# hijack-fram_C.net
KiCad netlist of a schematic drawn in EAGLE
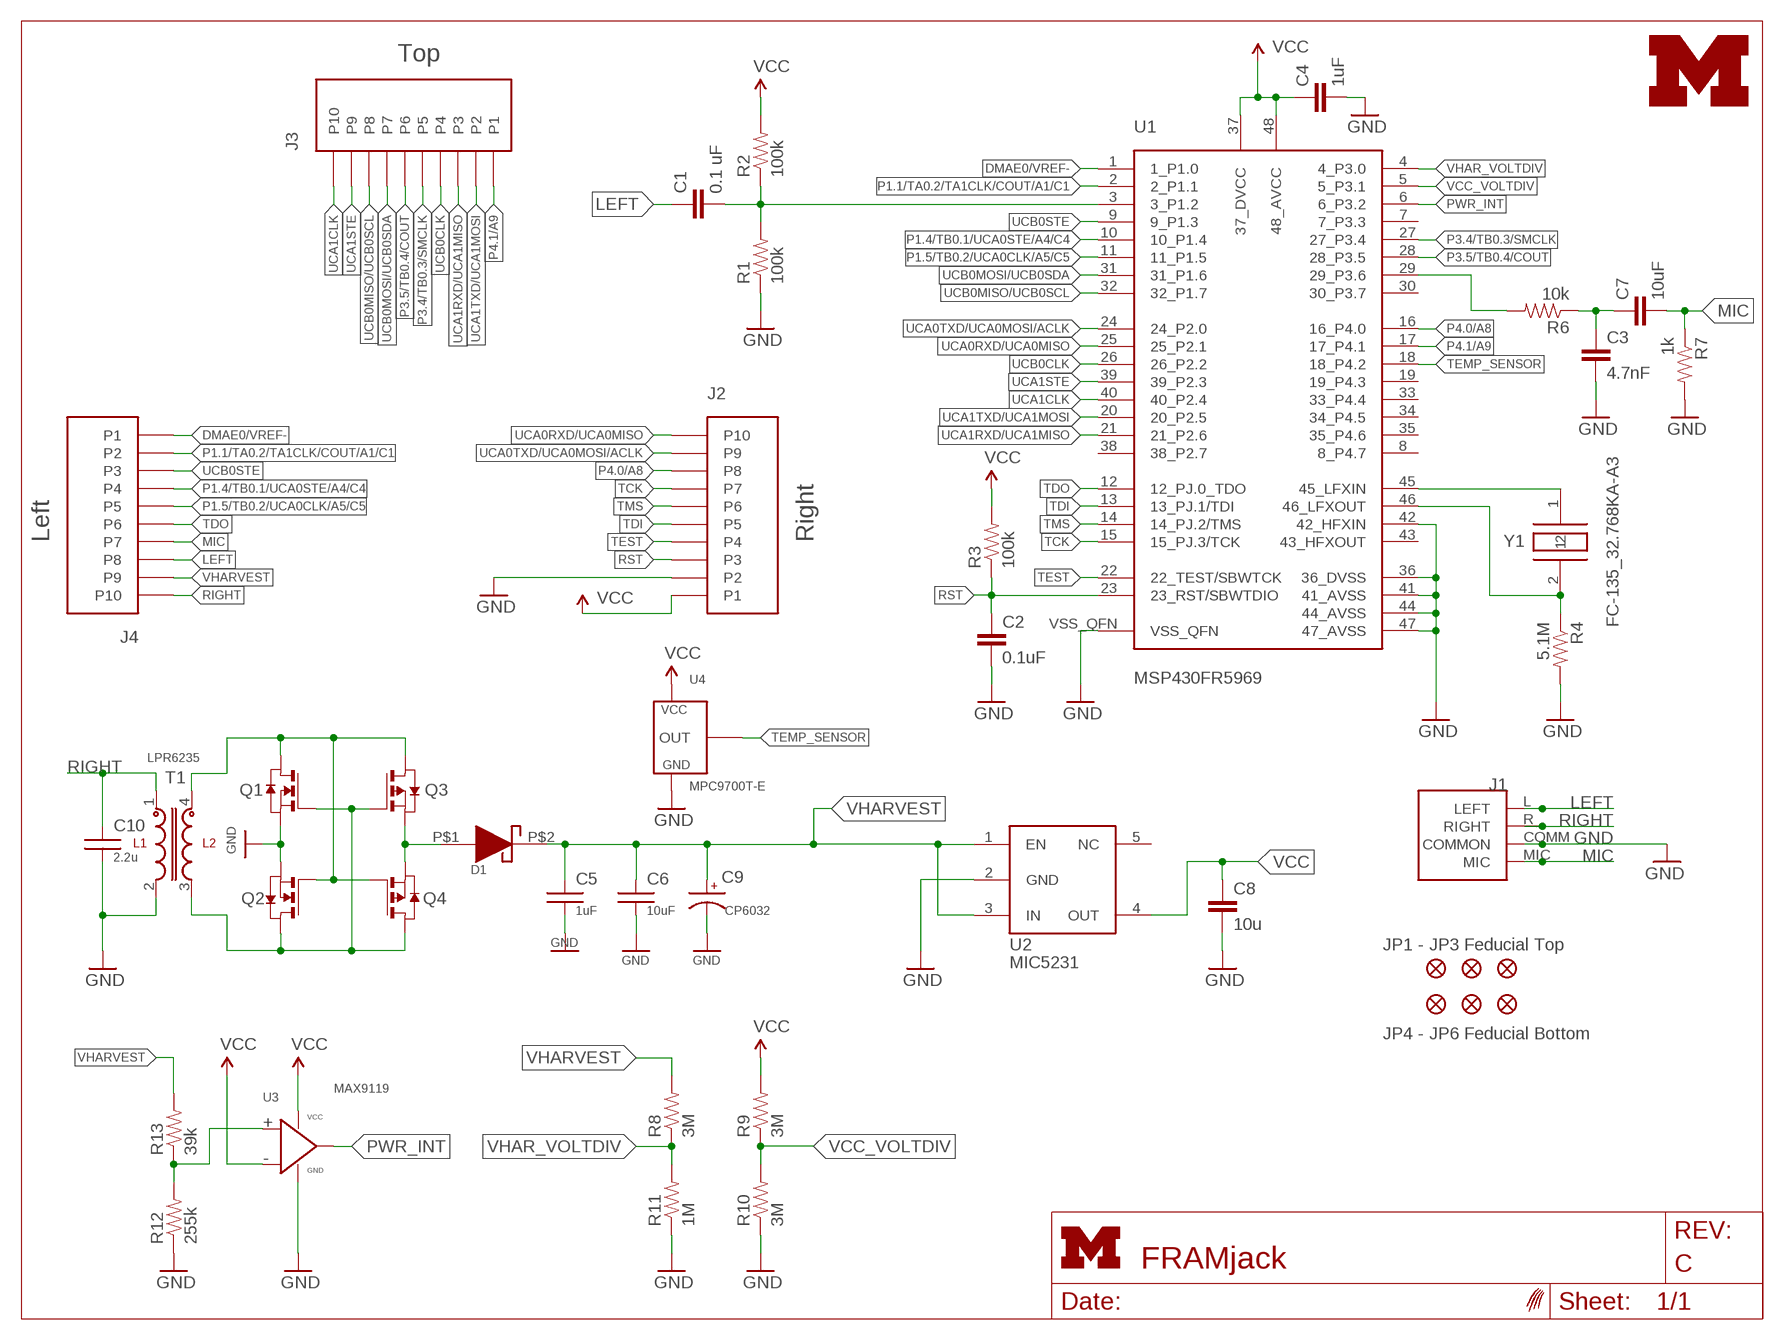
[diagram p0: schematic, sheet 1]

(export (version "E")
  (design (tool "Eeschema 10.0.6"))
  (components
    (comp (ref "C1")
      (value "0.1 uF")
      (footprint "eagle-import:0603-CAP")
      (libsource (lib "eagle-import") (part "CAP0603-CAP"))
    )
    (comp (ref "C2")
      (value "0.1uF")
      (footprint "eagle-import:0603-CAP")
      (libsource (lib "eagle-import") (part "CAP0603-CAP"))
    )
    (comp (ref "C3")
      (value "4.7nF")
      (footprint "eagle-import:0603-CAP")
      (libsource (lib "eagle-import") (part "CAP0603-CAP"))
    )
    (comp (ref "C4")
      (value "1uF")
      (footprint "eagle-import:0603-CAP")
      (libsource (lib "eagle-import") (part "CAP0603-CAP"))
    )
    (comp (ref "C5")
      (value "1uF")
      (footprint "eagle-import:C0603")
      (libsource (lib "eagle-import") (part "C0603"))
    )
    (comp (ref "C6")
      (value "10uF")
      (footprint "eagle-import:C0603")
      (libsource (lib "eagle-import") (part "C0603"))
    )
    (comp (ref "C7")
      (value "10uF")
      (footprint "eagle-import:0603-CAP")
      (libsource (lib "eagle-import") (part "CAP0603-CAP"))
    )
    (comp (ref "C8")
      (value "10u")
      (footprint "eagle-import:C0603")
      (libsource (lib "eagle-import") (part "C-EUC0603"))
    )
    (comp (ref "C9")
      (value "CP6032")
      (footprint "eagle-import:CT6032")
      (libsource (lib "eagle-import") (part "CP6032"))
    )
    (comp (ref "C10")
      (value "2.2u")
      (footprint "eagle-import:C0603")
      (libsource (lib "eagle-import") (part "C0603"))
    )
    (comp (ref "D1")
      (value "B5818WS-SCHOTTKY-DIODE")
      (footprint "eagle-import:SOD-323")
      (libsource (lib "eagle-import") (part "B5818WS-SCHOTTKY-DIODE"))
    )
    (comp (ref "J1")
      (value "3.5JACK4CONNSUNSTONE_QUICKTURN")
      (footprint "eagle-import:PLUGBOARDCONNECTOR_SUNSTONE")
      (libsource (lib "eagle-import") (part "3.5JACK4CONNSUNSTONE_QUICKTURN"))
    )
    (comp (ref "J2")
      (value "HEADER10POS")
      (footprint "eagle-import:10PIN2MMHEADER")
      (libsource (lib "eagle-import") (part "HEADER10POS"))
    )
    (comp (ref "J3")
      (value "HEADER10POS")
      (footprint "eagle-import:10PIN2MMHEADER")
      (libsource (lib "eagle-import") (part "HEADER10POS"))
    )
    (comp (ref "J4")
      (value "HEADER10POS")
      (footprint "eagle-import:10PIN2MMHEADER")
      (libsource (lib "eagle-import") (part "HEADER10POS"))
    )
    (comp (ref "JP1")
      (value "FIDUCIAL1X2")
      (footprint "eagle-import:FIDUCIAL-1X2")
      (libsource (lib "eagle-import") (part "FIDUCIAL1X2"))
    )
    (comp (ref "JP2")
      (value "FIDUCIAL1X2")
      (footprint "eagle-import:FIDUCIAL-1X2")
      (libsource (lib "eagle-import") (part "FIDUCIAL1X2"))
    )
    (comp (ref "JP3")
      (value "FIDUCIAL1X2")
      (footprint "eagle-import:FIDUCIAL-1X2")
      (libsource (lib "eagle-import") (part "FIDUCIAL1X2"))
    )
    (comp (ref "JP4")
      (value "FIDUCIAL1X2")
      (footprint "eagle-import:FIDUCIAL-1X2")
      (libsource (lib "eagle-import") (part "FIDUCIAL1X2"))
    )
    (comp (ref "JP5")
      (value "FIDUCIAL1X2")
      (footprint "eagle-import:FIDUCIAL-1X2")
      (libsource (lib "eagle-import") (part "FIDUCIAL1X2"))
    )
    (comp (ref "JP6")
      (value "FIDUCIAL1X2")
      (footprint "eagle-import:FIDUCIAL-1X2")
      (libsource (lib "eagle-import") (part "FIDUCIAL1X2"))
    )
    (comp (ref "Q1")
      (value "NMOSSOT23")
      (footprint "eagle-import:SOT-23")
      (libsource (lib "eagle-import") (part "NMOSSOT23"))
    )
    (comp (ref "Q2")
      (value "NMOSSOT23")
      (footprint "eagle-import:SOT-23")
      (libsource (lib "eagle-import") (part "NMOSSOT23"))
    )
    (comp (ref "Q3")
      (value "PMOSSOT23")
      (footprint "eagle-import:SOT-23")
      (libsource (lib "eagle-import") (part "PMOSSOT23"))
    )
    (comp (ref "Q4")
      (value "PMOSSOT23")
      (footprint "eagle-import:SOT-23")
      (libsource (lib "eagle-import") (part "PMOSSOT23"))
    )
    (comp (ref "R1")
      (value "100k")
      (footprint "eagle-import:0603-RES")
      (libsource (lib "eagle-import") (part "RESISTOR0603-RES"))
    )
    (comp (ref "R2")
      (value "100k")
      (footprint "eagle-import:0603-RES")
      (libsource (lib "eagle-import") (part "RESISTOR0603-RES"))
    )
    (comp (ref "R3")
      (value "100k")
      (footprint "eagle-import:0603-RES")
      (libsource (lib "eagle-import") (part "RESISTOR0603-RES"))
    )
    (comp (ref "R4")
      (value "5.1M")
      (footprint "eagle-import:0603-RES")
      (libsource (lib "eagle-import") (part "RESISTOR0603-RES"))
    )
    (comp (ref "R6")
      (value "10k")
      (footprint "eagle-import:0603-RES")
      (libsource (lib "eagle-import") (part "RESISTOR0603-RES"))
    )
    (comp (ref "R7")
      (value "1k")
      (footprint "eagle-import:0603-RES")
      (libsource (lib "eagle-import") (part "RESISTOR0603-RES"))
    )
    (comp (ref "R8")
      (value "3M")
      (footprint "eagle-import:0603-RES")
      (libsource (lib "eagle-import") (part "RESISTOR0603-RES"))
    )
    (comp (ref "R9")
      (value "3M")
      (footprint "eagle-import:0603-RES")
      (libsource (lib "eagle-import") (part "RESISTOR0603-RES"))
    )
    (comp (ref "R10")
      (value "3M")
      (footprint "eagle-import:0603-RES")
      (libsource (lib "eagle-import") (part "RESISTOR0603-RES"))
    )
    (comp (ref "R11")
      (value "1M")
      (footprint "eagle-import:0603-RES")
      (libsource (lib "eagle-import") (part "RESISTOR0603-RES"))
    )
    (comp (ref "R12")
      (value "255k")
      (footprint "eagle-import:0603-RES")
      (libsource (lib "eagle-import") (part "RESISTOR0603-RES"))
    )
    (comp (ref "R13")
      (value "39k")
      (footprint "eagle-import:0603-RES")
      (libsource (lib "eagle-import") (part "RESISTOR0603-RES"))
    )
    (comp (ref "T1")
      (value "LPR6235")
      (footprint "eagle-import:LPR6235")
      (libsource (lib "eagle-import") (part "LPR6235"))
    )
    (comp (ref "U$1")
      (value "WOLVERINE")
      (footprint "eagle-import:WOLVERINE")
      (libsource (lib "eagle-import") (part "WOLVERINE"))
    )
    (comp (ref "U$4")
      (value "UMICH_SOLID_SMALL")
      (footprint "eagle-import:UMICH_SOLID_75MIL")
      (libsource (lib "eagle-import") (part "UMICH_SOLID_SMALL"))
    )
    (comp (ref "U1")
      (value "MSP430FR5969")
      (footprint "eagle-import:RGZ(S-PQFP-N48)")
      (libsource (lib "eagle-import") (part "MSP430FR5969"))
    )
    (comp (ref "U2")
      (value "MIC5231")
      (footprint "eagle-import:SOT23-5")
      (libsource (lib "eagle-import") (part "MIC5231"))
    )
    (comp (ref "U3")
      (value "MAX9119")
      (footprint "eagle-import:SC70-5")
      (libsource (lib "eagle-import") (part "MAX9119"))
    )
    (comp (ref "U4")
      (value "MPC9700T-E")
      (footprint "eagle-import:SOT-23")
      (libsource (lib "eagle-import") (part "MPC9700T-E"))
    )
    (comp (ref "Y1")
      (value "FC-135_32.768KA-A3")
      (footprint "eagle-import:FC-135")
      (libsource (lib "eagle-import") (part "FC-135_32.768KA-A3"))
    )
  )
  (nets
    (net (code "1") (name "DMAE0{slash}VREF-") (class "Default")
      (node (ref "J4") (pin "P1") (pinfunction "P1_P1") (pintype "bidirectional"))
      (node (ref "U1") (pin "1") (pinfunction "1_P1.0_1") (pintype "bidirectional"))
    )
    (net (code "2") (name "GND") (class "Default")
      (node (ref "C10") (pin "2") (pinfunction "2_2") (pintype "bidirectional"))
      (node (ref "C2") (pin "2") (pinfunction "2_2") (pintype "passive"))
      (node (ref "C3") (pin "2") (pinfunction "2_2") (pintype "passive"))
      (node (ref "C4") (pin "2") (pinfunction "2_2") (pintype "passive"))
      (node (ref "C5") (pin "2") (pinfunction "2_2") (pintype "bidirectional"))
      (node (ref "C6") (pin "2") (pinfunction "2_2") (pintype "bidirectional"))
      (node (ref "C8") (pin "2") (pinfunction "2_2") (pintype "passive"))
      (node (ref "C9") (pin "-") (pinfunction "-_-") (pintype "bidirectional"))
      (node (ref "J1") (pin "COMM") (pinfunction "COMMON_COMM") (pintype "power_in"))
      (node (ref "J2") (pin "P2") (pinfunction "P2_P2") (pintype "bidirectional"))
      (node (ref "Q1") (pin "2") (pinfunction "S_2") (pintype "passive"))
      (node (ref "Q2") (pin "2") (pinfunction "S_2") (pintype "passive"))
      (node (ref "R1") (pin "1") (pinfunction "1_1") (pintype "passive"))
      (node (ref "R10") (pin "1") (pinfunction "1_1") (pintype "passive"))
      (node (ref "R11") (pin "1") (pinfunction "1_1") (pintype "passive"))
      (node (ref "R12") (pin "1") (pinfunction "1_1") (pintype "passive"))
      (node (ref "R4") (pin "2") (pinfunction "2_2") (pintype "passive"))
      (node (ref "R7") (pin "2") (pinfunction "2_2") (pintype "passive"))
      (node (ref "T1") (pin "2") (pinfunction "2_2") (pintype "bidirectional"))
      (node (ref "U1") (pin "36") (pinfunction "36_DVSS_36") (pintype "bidirectional"))
      (node (ref "U1") (pin "41") (pinfunction "41_AVSS_41") (pintype "bidirectional"))
      (node (ref "U1") (pin "42") (pinfunction "42_HFXIN_42") (pintype "bidirectional"))
      (node (ref "U1") (pin "44") (pinfunction "44_AVSS_44") (pintype "bidirectional"))
      (node (ref "U1") (pin "47") (pinfunction "47_AVSS_47") (pintype "bidirectional"))
      (node (ref "U1") (pin "VSS_QFN") (pinfunction "VSS_QFN_VSS_QFN") (pintype "bidirectional"))
      (node (ref "U2") (pin "2") (pinfunction "GND_2") (pintype "bidirectional"))
      (node (ref "U3") (pin "2") (pinfunction "GND_2") (pintype "bidirectional"))
      (node (ref "U4") (pin "GND") (pinfunction "GND_GND") (pintype "bidirectional"))
    )
    (net (code "3") (name "LEFT") (class "Default")
      (node (ref "C1") (pin "1") (pinfunction "1_1") (pintype "passive"))
      (node (ref "J1") (pin "L") (pinfunction "LEFT_L") (pintype "output"))
      (node (ref "J4") (pin "P8") (pinfunction "P8_P8") (pintype "bidirectional"))
    )
    (net (code "4") (name "MIC") (class "Default")
      (node (ref "C7") (pin "2") (pinfunction "2_2") (pintype "passive"))
      (node (ref "J1") (pin "MIC") (pinfunction "MIC_MIC") (pintype "input"))
      (node (ref "J4") (pin "P7") (pinfunction "P7_P7") (pintype "bidirectional"))
      (node (ref "R7") (pin "1") (pinfunction "1_1") (pintype "passive"))
    )
    (net (code "5") (name "Net-(C3-Pad1)") (class "Default")
      (node (ref "C3") (pin "1") (pinfunction "1_1") (pintype "passive"))
      (node (ref "C7") (pin "1") (pinfunction "1_1") (pintype "passive"))
      (node (ref "R6") (pin "1") (pinfunction "1_1") (pintype "passive"))
    )
    (net (code "6") (name "Net-(D1-A)") (class "Default")
      (node (ref "D1") (pin "P$1") (pinfunction "A_P$1") (pintype "bidirectional"))
      (node (ref "Q3") (pin "2") (pinfunction "S_2") (pintype "passive"))
      (node (ref "Q4") (pin "2") (pinfunction "S_2") (pintype "passive"))
    )
    (net (code "7") (name "Net-(Q1-D)") (class "Default")
      (node (ref "Q1") (pin "1") (pinfunction "D_1") (pintype "passive"))
      (node (ref "Q2") (pin "3") (pinfunction "G_3") (pintype "passive"))
      (node (ref "Q3") (pin "1") (pinfunction "D_1") (pintype "passive"))
      (node (ref "Q4") (pin "3") (pinfunction "G_3") (pintype "passive"))
      (node (ref "T1") (pin "4") (pinfunction "4_4") (pintype "bidirectional"))
    )
    (net (code "8") (name "Net-(Q1-G)") (class "Default")
      (node (ref "Q1") (pin "3") (pinfunction "G_3") (pintype "passive"))
      (node (ref "Q2") (pin "1") (pinfunction "D_1") (pintype "passive"))
      (node (ref "Q3") (pin "3") (pinfunction "G_3") (pintype "passive"))
      (node (ref "Q4") (pin "1") (pinfunction "D_1") (pintype "passive"))
      (node (ref "T1") (pin "3") (pinfunction "3_3") (pintype "bidirectional"))
    )
    (net (code "9") (name "Net-(U1-3_P1.2)") (class "Default")
      (node (ref "C1") (pin "2") (pinfunction "2_2") (pintype "passive"))
      (node (ref "R1") (pin "2") (pinfunction "2_2") (pintype "passive"))
      (node (ref "R2") (pin "1") (pinfunction "1_1") (pintype "passive"))
      (node (ref "U1") (pin "3") (pinfunction "3_P1.2_3") (pintype "bidirectional"))
    )
    (net (code "10") (name "Net-(U1-29_P3.6)") (class "Default")
      (node (ref "R6") (pin "2") (pinfunction "2_2") (pintype "passive"))
      (node (ref "U1") (pin "29") (pinfunction "29_P3.6_29") (pintype "bidirectional"))
    )
    (net (code "11") (name "Net-(U1-45_LFXIN)") (class "Default")
      (node (ref "U1") (pin "45") (pinfunction "45_LFXIN_45") (pintype "bidirectional"))
      (node (ref "Y1") (pin "1") (pinfunction "1_1") (pintype "bidirectional"))
    )
    (net (code "12") (name "Net-(U1-46_LFXOUT)") (class "Default")
      (node (ref "R4") (pin "1") (pinfunction "1_1") (pintype "passive"))
      (node (ref "U1") (pin "46") (pinfunction "46_LFXOUT_46") (pintype "bidirectional"))
      (node (ref "Y1") (pin "2") (pinfunction "2_2") (pintype "bidirectional"))
    )
    (net (code "13") (name "Net-(U3-IN+)") (class "Default")
      (node (ref "R12") (pin "2") (pinfunction "2_2") (pintype "passive"))
      (node (ref "R13") (pin "1") (pinfunction "1_1") (pintype "passive"))
      (node (ref "U3") (pin "3") (pinfunction "IN+_3") (pintype "bidirectional"))
    )
    (net (code "14") (name "P1.1{slash}TA0.2{slash}TA1CLK{slash}COUT{slash}A1{slash}C1") (class "Default")
      (node (ref "J4") (pin "P2") (pinfunction "P2_P2") (pintype "bidirectional"))
      (node (ref "U1") (pin "2") (pinfunction "2_P1.1_2") (pintype "bidirectional"))
    )
    (net (code "15") (name "P1.4{slash}TB0.1{slash}UCA0STE{slash}A4{slash}C4") (class "Default")
      (node (ref "J4") (pin "P4") (pinfunction "P4_P4") (pintype "bidirectional"))
      (node (ref "U1") (pin "10") (pinfunction "10_P1.4_10") (pintype "bidirectional"))
    )
    (net (code "16") (name "P1.5{slash}TB0.2{slash}UCA0CLK{slash}A5{slash}C5") (class "Default")
      (node (ref "J4") (pin "P5") (pinfunction "P5_P5") (pintype "bidirectional"))
      (node (ref "U1") (pin "11") (pinfunction "11_P1.5_11") (pintype "bidirectional"))
    )
    (net (code "17") (name "P3.4{slash}TB0.3{slash}SMCLK") (class "Default")
      (node (ref "J3") (pin "P5") (pinfunction "P5_P5") (pintype "bidirectional"))
      (node (ref "U1") (pin "27") (pinfunction "27_P3.4_27") (pintype "bidirectional"))
    )
    (net (code "18") (name "P3.5{slash}TB0.4{slash}COUT") (class "Default")
      (node (ref "J3") (pin "P6") (pinfunction "P6_P6") (pintype "bidirectional"))
      (node (ref "U1") (pin "28") (pinfunction "28_P3.5_28") (pintype "bidirectional"))
    )
    (net (code "19") (name "P4.0{slash}A8") (class "Default")
      (node (ref "J2") (pin "P8") (pinfunction "P8_P8") (pintype "bidirectional"))
      (node (ref "U1") (pin "16") (pinfunction "16_P4.0_16") (pintype "bidirectional"))
    )
    (net (code "20") (name "P4.1{slash}A9") (class "Default")
      (node (ref "J3") (pin "P1") (pinfunction "P1_P1") (pintype "bidirectional"))
      (node (ref "U1") (pin "17") (pinfunction "17_P4.1_17") (pintype "bidirectional"))
    )
    (net (code "21") (name "PWR_INT") (class "Default")
      (node (ref "U1") (pin "6") (pinfunction "6_P3.2_6") (pintype "bidirectional"))
      (node (ref "U3") (pin "1") (pinfunction "OUT_1") (pintype "bidirectional"))
    )
    (net (code "22") (name "RIGHT") (class "Default")
      (node (ref "C10") (pin "1") (pinfunction "1_1") (pintype "bidirectional"))
      (node (ref "J1") (pin "R") (pinfunction "RIGHT_R") (pintype "output"))
      (node (ref "J4") (pin "P10") (pinfunction "P10_P10") (pintype "bidirectional"))
      (node (ref "T1") (pin "1") (pinfunction "1_1") (pintype "bidirectional"))
    )
    (net (code "23") (name "RST") (class "Default")
      (node (ref "C2") (pin "1") (pinfunction "1_1") (pintype "passive"))
      (node (ref "J2") (pin "P3") (pinfunction "P3_P3") (pintype "bidirectional"))
      (node (ref "R3") (pin "1") (pinfunction "1_1") (pintype "passive"))
      (node (ref "U1") (pin "23") (pinfunction "23_RST/SBWTDIO_23") (pintype "bidirectional"))
    )
    (net (code "24") (name "TCK") (class "Default")
      (node (ref "J2") (pin "P7") (pinfunction "P7_P7") (pintype "bidirectional"))
      (node (ref "U1") (pin "15") (pinfunction "15_PJ.3/TCK_15") (pintype "bidirectional"))
    )
    (net (code "25") (name "TDI") (class "Default")
      (node (ref "J2") (pin "P5") (pinfunction "P5_P5") (pintype "bidirectional"))
      (node (ref "U1") (pin "13") (pinfunction "13_PJ.1/TDI_13") (pintype "bidirectional"))
    )
    (net (code "26") (name "TDO") (class "Default")
      (node (ref "J4") (pin "P6") (pinfunction "P6_P6") (pintype "bidirectional"))
      (node (ref "U1") (pin "12") (pinfunction "12_PJ.0_TDO_12") (pintype "bidirectional"))
    )
    (net (code "27") (name "TEMP_SENSOR") (class "Default")
      (node (ref "U1") (pin "18") (pinfunction "18_P4.2_18") (pintype "bidirectional"))
      (node (ref "U4") (pin "VOUT") (pinfunction "OUT_VOUT") (pintype "bidirectional"))
    )
    (net (code "28") (name "TEST") (class "Default")
      (node (ref "J2") (pin "P4") (pinfunction "P4_P4") (pintype "bidirectional"))
      (node (ref "U1") (pin "22") (pinfunction "22_TEST/SBWTCK_22") (pintype "bidirectional"))
    )
    (net (code "29") (name "TMS") (class "Default")
      (node (ref "J2") (pin "P6") (pinfunction "P6_P6") (pintype "bidirectional"))
      (node (ref "U1") (pin "14") (pinfunction "14_PJ.2/TMS_14") (pintype "bidirectional"))
    )
    (net (code "30") (name "UCA0RXD{slash}UCA0MISO") (class "Default")
      (node (ref "J2") (pin "P10") (pinfunction "P10_P10") (pintype "bidirectional"))
      (node (ref "U1") (pin "25") (pinfunction "25_P2.1_25") (pintype "bidirectional"))
    )
    (net (code "31") (name "UCA0TXD{slash}UCA0MOSI{slash}ACLK") (class "Default")
      (node (ref "J2") (pin "P9") (pinfunction "P9_P9") (pintype "bidirectional"))
      (node (ref "U1") (pin "24") (pinfunction "24_P2.0_24") (pintype "bidirectional"))
    )
    (net (code "32") (name "UCA1CLK") (class "Default")
      (node (ref "J3") (pin "P10") (pinfunction "P10_P10") (pintype "bidirectional"))
      (node (ref "U1") (pin "40") (pinfunction "40_P2.4_40") (pintype "bidirectional"))
    )
    (net (code "33") (name "UCA1RXD{slash}UCA1MISO") (class "Default")
      (node (ref "J3") (pin "P3") (pinfunction "P3_P3") (pintype "bidirectional"))
      (node (ref "U1") (pin "21") (pinfunction "21_P2.6_21") (pintype "bidirectional"))
    )
    (net (code "34") (name "UCA1STE") (class "Default")
      (node (ref "J3") (pin "P9") (pinfunction "P9_P9") (pintype "bidirectional"))
      (node (ref "U1") (pin "39") (pinfunction "39_P2.3_39") (pintype "bidirectional"))
    )
    (net (code "35") (name "UCA1TXD{slash}UCA1MOSI") (class "Default")
      (node (ref "J3") (pin "P2") (pinfunction "P2_P2") (pintype "bidirectional"))
      (node (ref "U1") (pin "20") (pinfunction "20_P2.5_20") (pintype "bidirectional"))
    )
    (net (code "36") (name "UCB0CLK") (class "Default")
      (node (ref "J3") (pin "P4") (pinfunction "P4_P4") (pintype "bidirectional"))
      (node (ref "U1") (pin "26") (pinfunction "26_P2.2_26") (pintype "bidirectional"))
    )
    (net (code "37") (name "UCB0MISO{slash}UCB0SCL") (class "Default")
      (node (ref "J3") (pin "P8") (pinfunction "P8_P8") (pintype "bidirectional"))
      (node (ref "U1") (pin "32") (pinfunction "32_P1.7_32") (pintype "bidirectional"))
    )
    (net (code "38") (name "UCB0MOSI{slash}UCB0SDA") (class "Default")
      (node (ref "J3") (pin "P7") (pinfunction "P7_P7") (pintype "bidirectional"))
      (node (ref "U1") (pin "31") (pinfunction "31_P1.6_31") (pintype "bidirectional"))
    )
    (net (code "39") (name "UCB0STE") (class "Default")
      (node (ref "J4") (pin "P3") (pinfunction "P3_P3") (pintype "bidirectional"))
      (node (ref "U1") (pin "9") (pinfunction "9_P1.3_9") (pintype "bidirectional"))
    )
    (net (code "40") (name "VCC") (class "Default")
      (node (ref "C4") (pin "1") (pinfunction "1_1") (pintype "passive"))
      (node (ref "C8") (pin "1") (pinfunction "1_1") (pintype "passive"))
      (node (ref "J2") (pin "P1") (pinfunction "P1_P1") (pintype "bidirectional"))
      (node (ref "R2") (pin "2") (pinfunction "2_2") (pintype "passive"))
      (node (ref "R3") (pin "2") (pinfunction "2_2") (pintype "passive"))
      (node (ref "R9") (pin "2") (pinfunction "2_2") (pintype "passive"))
      (node (ref "U1") (pin "37") (pinfunction "37_DVCC_37") (pintype "bidirectional"))
      (node (ref "U1") (pin "48") (pinfunction "48_AVCC_48") (pintype "bidirectional"))
      (node (ref "U2") (pin "4") (pinfunction "OUT_4") (pintype "bidirectional"))
      (node (ref "U3") (pin "4") (pinfunction "IN-_4") (pintype "bidirectional"))
      (node (ref "U3") (pin "5") (pinfunction "VCC_5") (pintype "bidirectional"))
      (node (ref "U4") (pin "VDD") (pinfunction "VCC_VDD") (pintype "bidirectional"))
    )
    (net (code "41") (name "VCC_VOLTDIV") (class "Default")
      (node (ref "R10") (pin "2") (pinfunction "2_2") (pintype "passive"))
      (node (ref "R9") (pin "1") (pinfunction "1_1") (pintype "passive"))
      (node (ref "U1") (pin "5") (pinfunction "5_P3.1_5") (pintype "bidirectional"))
    )
    (net (code "42") (name "VHARVEST") (class "Default")
      (node (ref "C5") (pin "1") (pinfunction "1_1") (pintype "bidirectional"))
      (node (ref "C6") (pin "1") (pinfunction "1_1") (pintype "bidirectional"))
      (node (ref "C9") (pin "+") (pinfunction "+_+") (pintype "bidirectional"))
      (node (ref "D1") (pin "P$2") (pinfunction "C_P$2") (pintype "bidirectional"))
      (node (ref "J4") (pin "P9") (pinfunction "P9_P9") (pintype "bidirectional"))
      (node (ref "R13") (pin "2") (pinfunction "2_2") (pintype "passive"))
      (node (ref "R8") (pin "2") (pinfunction "2_2") (pintype "passive"))
      (node (ref "U2") (pin "1") (pinfunction "EN_1") (pintype "bidirectional"))
      (node (ref "U2") (pin "3") (pinfunction "IN_3") (pintype "bidirectional"))
    )
    (net (code "43") (name "VHAR_VOLTDIV") (class "Default")
      (node (ref "R11") (pin "2") (pinfunction "2_2") (pintype "passive"))
      (node (ref "R8") (pin "1") (pinfunction "1_1") (pintype "passive"))
      (node (ref "U1") (pin "4") (pinfunction "4_P3.0_4") (pintype "bidirectional"))
    )
    (net (code "44") (name "unconnected-(U1-7_P3.3-Pad7)") (class "Default")
      (node (ref "U1") (pin "7") (pinfunction "7_P3.3_7") (pintype "bidirectional"))
    )
    (net (code "45") (name "unconnected-(U1-8_P4.7-Pad8)") (class "Default")
      (node (ref "U1") (pin "8") (pinfunction "8_P4.7_8") (pintype "bidirectional"))
    )
    (net (code "46") (name "unconnected-(U1-19_P4.3-Pad19)") (class "Default")
      (node (ref "U1") (pin "19") (pinfunction "19_P4.3_19") (pintype "bidirectional"))
    )
    (net (code "47") (name "unconnected-(U1-30_P3.7-Pad30)") (class "Default")
      (node (ref "U1") (pin "30") (pinfunction "30_P3.7_30") (pintype "bidirectional"))
    )
    (net (code "48") (name "unconnected-(U1-33_P4.4-Pad33)") (class "Default")
      (node (ref "U1") (pin "33") (pinfunction "33_P4.4_33") (pintype "bidirectional"))
    )
    (net (code "49") (name "unconnected-(U1-34_P4.5-Pad34)") (class "Default")
      (node (ref "U1") (pin "34") (pinfunction "34_P4.5_34") (pintype "bidirectional"))
    )
    (net (code "50") (name "unconnected-(U1-35_P4.6-Pad35)") (class "Default")
      (node (ref "U1") (pin "35") (pinfunction "35_P4.6_35") (pintype "bidirectional"))
    )
    (net (code "51") (name "unconnected-(U1-38_P2.7-Pad38)") (class "Default")
      (node (ref "U1") (pin "38") (pinfunction "38_P2.7_38") (pintype "bidirectional"))
    )
    (net (code "52") (name "unconnected-(U1-43_HFXOUT-Pad43)") (class "Default")
      (node (ref "U1") (pin "43") (pinfunction "43_HFXOUT_43") (pintype "bidirectional"))
    )
    (net (code "53") (name "unconnected-(U2-NC-Pad5)") (class "Default")
      (node (ref "U2") (pin "5") (pinfunction "NC_5") (pintype "bidirectional"))
    )
  )
)
